# MCU.net
KiCad netlist of a schematic drawn in Altium Designer
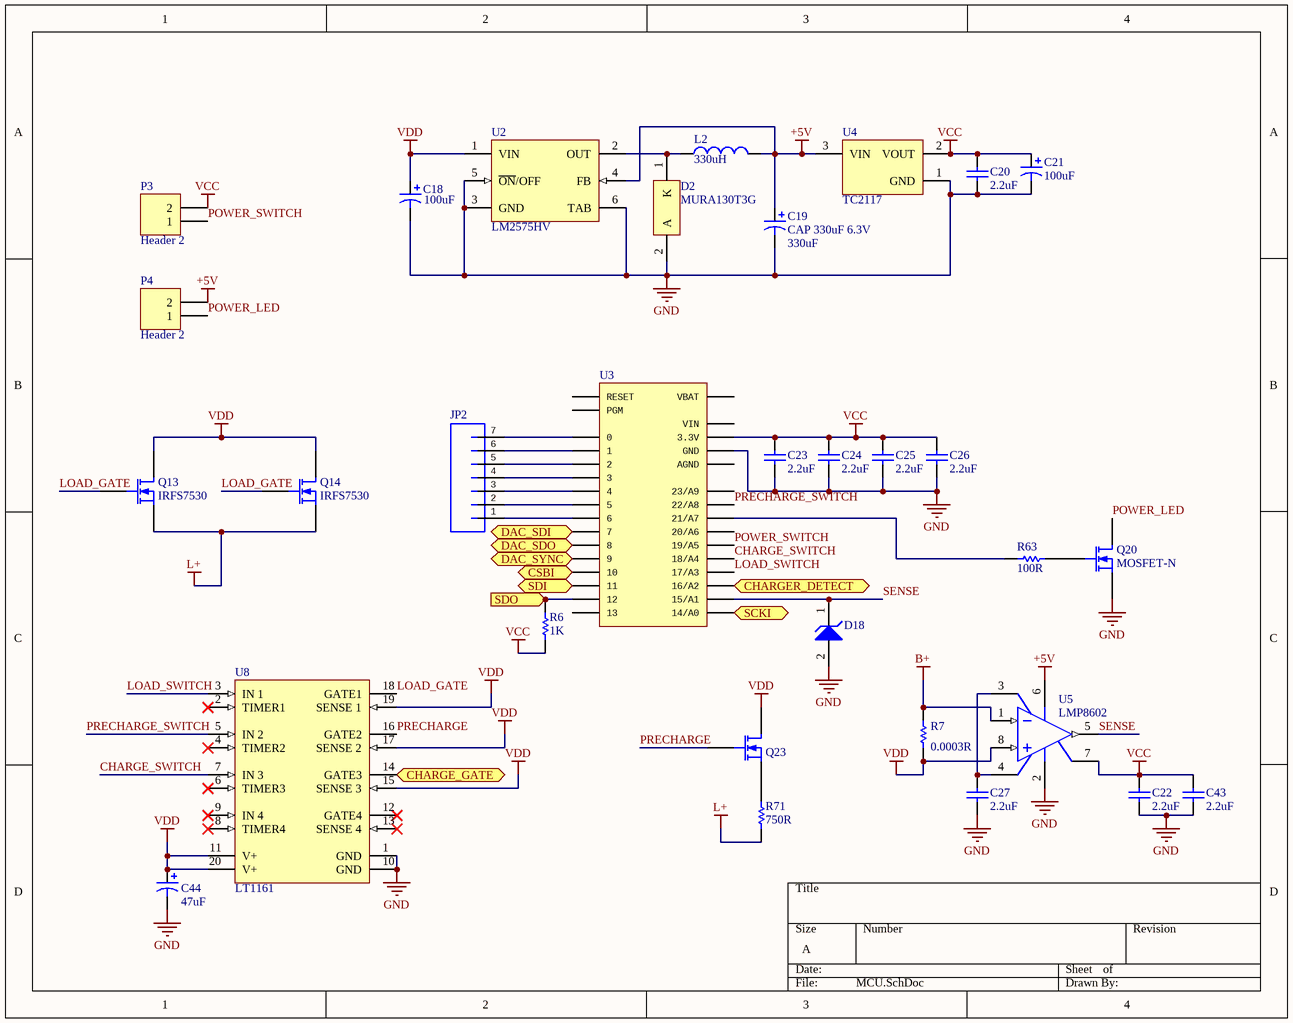
[diagram p0: MCU.SchDoc]

(export (version "E")
  (design (tool "Eeschema 10.0.6"))
  (components
    (comp (ref "C18")
      (value "100uF")
      (footprint "CAP 180uF 50V")
      (description "Polarized Capacitor (Axial)")
      (fields (field (name "PUBLISHER") "Altium Limited"))
      (libsource (lib "Components") (part "CAP 100uF 63V"))
    )
    (comp (ref "C19")
      (value "CAP 330uF 6.3V")
      (footprint "CAP 300uF 6.3V")
      (description "Polarized Capacitor (Axial)")
      (fields (field (name "ALTIUM_VALUE") "330uF") (field (name "PUBLISHER") "Altium Limited"))
      (libsource (lib "Components") (part "CAP 330uF 6.3V"))
    )
    (comp (ref "C20")
      (value "2.2uF")
      (footprint "CAPC0603(1608)55_N")
      (description "CAP 2.2uF 16V Â±10% 0603 (1608 Metric) Thickness 0.55mm SMD")
      (fields (field (name "TOLERANCE") "Â±10%"))
      (libsource (lib "Altium Content Vault") (part "CMP-1035-02762-1"))
    )
    (comp (ref "C21")
      (value "100uF")
      (footprint "AVX-CAPC7343_V")
      (description "Capacitor, Tantalum, 220uF 10% 10V MCCT-D (7343-31)")
      (fields (field (name "PARTNUMBER") "TAJD227K010R") (field (name "MANUFACTURER") "AVX"))
      (libsource (lib "Altium Content Vault") (part "CMP-0279-00002-1"))
    )
    (comp (ref "C22")
      (value "2.2uF")
      (footprint "CAPC0603(1608)55_M")
      (description "CAP 2.2uF 4V Â±10% 0603 (1608 Metric) Thickness 0.55mm SMD")
      (fields (field (name "TOLERANCE") "Â±10%"))
      (libsource (lib "Altium Content Vault") (part "CAP"))
    )
    (comp (ref "C23")
      (value "2.2uF")
      (footprint "CAPC0603(1608)55_N")
      (description "CAP 2.2uF 16V Â±10% 0603 (1608 Metric) Thickness 0.55mm SMD")
      (fields (field (name "TOLERANCE") "Â±10%"))
      (libsource (lib "Altium Content Vault") (part "CMP-1035-02762-1"))
    )
    (comp (ref "C24")
      (value "2.2uF")
      (footprint "CAPC0603(1608)55_N")
      (description "CAP 2.2uF 16V Â±10% 0603 (1608 Metric) Thickness 0.55mm SMD")
      (fields (field (name "TOLERANCE") "Â±10%"))
      (libsource (lib "Altium Content Vault") (part "CMP-1035-02762-1"))
    )
    (comp (ref "C25")
      (value "2.2uF")
      (footprint "CAPC0603(1608)55_N")
      (description "CAP 2.2uF 16V Â±10% 0603 (1608 Metric) Thickness 0.55mm SMD")
      (fields (field (name "TOLERANCE") "Â±10%"))
      (libsource (lib "Altium Content Vault") (part "CMP-1035-02762-1"))
    )
    (comp (ref "C26")
      (value "2.2uF")
      (footprint "CAPC0603(1608)55_N")
      (description "CAP 2.2uF 16V Â±10% 0603 (1608 Metric) Thickness 0.55mm SMD")
      (fields (field (name "TOLERANCE") "Â±10%"))
      (libsource (lib "Altium Content Vault") (part "CMP-1035-02762-1"))
    )
    (comp (ref "C27")
      (value "2.2uF")
      (footprint "CAPC0603(1608)55_N")
      (description "CAP 2.2uF 16V Â±10% 0603 (1608 Metric) Thickness 0.55mm SMD")
      (fields (field (name "TOLERANCE") "Â±10%"))
      (libsource (lib "Altium Content Vault") (part "CMP-1035-02762-1"))
    )
    (comp (ref "C43")
      (value "2.2uF")
      (footprint "CAPC0603(1608)55_M")
      (description "CAP 2.2uF 4V Â±10% 0603 (1608 Metric) Thickness 0.55mm SMD")
      (fields (field (name "TOLERANCE") "Â±10%"))
      (libsource (lib "Altium Content Vault") (part "CAP"))
    )
    (comp (ref "C44")
      (value "47uF")
      (footprint "CAP 300uF 6.3V")
      (description "Polarized Capacitor (Axial)")
      (fields (field (name "PUBLISHER") "Altium Limited"))
      (libsource (lib "Components") (part "CAP 47uF 50V"))
    )
    (comp (ref "D2")
      (value "MURA130T3G")
      (footprint "ONSC-SMA-2-403D-02_V")
      (description "Surface Mount Ultrafast Power Rectifier, 2-Pin SMA, Pb-Free, Tape and Reel")
      (fields (field (name "MANUFACTURER") "On Semiconductor"))
      (libsource (lib "Altium Content Vault") (part "ONSC-D-K1A2-2_A"))
    )
    (comp (ref "D18")
      (value "~")
      (footprint "ONSC-SOD-323-2-477-02_V")
      (description "Zener Voltage Regulator, 300 mW, Tight Tolerance Portfolio, 2-Pin SOD-323, Pb-Free, Tape and Reel")
      (fields (field (name "PARTNUMBER") "MM3Z3V3ST1G") (field (name "MANUFACTURER") "On Semiconductor"))
      (libsource (lib "Altium Inc") (part "ONSC-K1A2-2"))
    )
    (comp (ref "JP2") (value "~") (footprint "JST-7-PTH") (libsource (lib "Components") (part "JST_7_RIGHT")))
    (comp (ref "L2")
      (value "330uH")
      (footprint "SDR1307")
      (description "Inductor")
      (fields (field (name "PUBLISHER") "Altium Limited"))
      (libsource (lib "Components") (part "SDR1307-331KL"))
    )
    (comp (ref "P3")
      (value "Header 2")
      (footprint "HDR1X2")
      (description "Header, 2-Pin")
      (fields (field (name "PUBLISHER") "Altium Limited"))
      (libsource (lib "Miscellaneous Connectors") (part "Header 2"))
    )
    (comp (ref "P4")
      (value "Header 2")
      (footprint "HDR1X2")
      (description "Header, 2-Pin")
      (fields (field (name "PUBLISHER") "Altium Limited"))
      (libsource (lib "Miscellaneous Connectors") (part "Header 2"))
    )
    (comp (ref "Q13")
      (value "IRFS7530")
      (footprint "DPAK127P1525X483-7N")
      (description "N-Channel MOSFET")
      (fields (field (name "PUBLISHER") "Altium Limited"))
      (libsource (lib "Components") (part "IRFS7530"))
    )
    (comp (ref "Q14")
      (value "IRFS7530")
      (footprint "DPAK127P1525X483-7N")
      (description "N-Channel MOSFET")
      (fields (field (name "PUBLISHER") "Altium Limited"))
      (libsource (lib "Components") (part "IRFS7530"))
    )
    (comp (ref "Q20")
      (value "MOSFET-N")
      (footprint "SOT23-3")
      (description "N-Channel MOSFET")
      (fields (field (name "PUBLISHER") "Altium Limited"))
      (libsource (lib "Components") (part "MOSFET-N"))
    )
    (comp (ref "Q23")
      (value "MOSFET-N")
      (footprint "SOT23-3")
      (description "N-Channel MOSFET")
      (fields (field (name "PUBLISHER") "Altium Limited"))
      (libsource (lib "Components") (part "MOSFET-N"))
    )
    (comp (ref "R6")
      (value "1K")
      (footprint "RESC0603(1608)_L")
      (description "1K 0.1W 5% 0603 (1608 Metric)  SMD")
      (fields (field (name "TOLERANCE") "5 %") (field (name "POWER") "0.1 W"))
      (libsource (lib "Altium Content Vault") (part "RES"))
    )
    (comp (ref "R7")
      (value "0.0003R")
      (footprint "WSLP5931")
      (description "Resistor")
      (fields (field (name "PUBLISHER") "Altium Limited"))
      (libsource (lib "Components") (part "SHUNT"))
    )
    (comp (ref "R63")
      (value "100R")
      (footprint "RESC0603(1608)_L")
      (description "100R 0.1W 5% 0603 (1608 Metric)  SMD")
      (fields (field (name "TOLERANCE") "5 %") (field (name "POWER") "0.1 W"))
      (libsource (lib "Altium Content Vault") (part "RES"))
    )
    (comp (ref "R71")
      (value "750R")
      (footprint "RESC2512(6432)_N")
      (description "750R 1W 1% 2512 (6432 Metric)  SMD")
      (fields (field (name "TOLERANCE") "1 %") (field (name "POWER") "1 W"))
      (libsource (lib "Altium Content Vault") (part "RES"))
    )
    (comp (ref "U2")
      (value "LM2575HV")
      (footprint "TS5B_L")
      (description "SIMPLE SWITCHERÂ® 1A Step-Down Voltage Regulator, 5-pin TO-263, Pb-Free")
      (fields (field (name "MANUFACTURER") "National Semiconductor"))
      (libsource (lib "Altium Content Vault") (part "PM-REG-LM2575HVS-12"))
    )
    (comp (ref "U3")
      (value "~")
      (footprint "TEENSY_3.0_BASIC")
      (libsource (lib "Components") (part "TEENSY_3.0_BASIC"))
    )
    (comp (ref "U4")
      (value "TC2117")
      (footprint "SOT-223-DB3_M")
      (libsource (lib "Components") (part "PM-LINEREG-TC2117-IL4"))
    )
    (comp (ref "U5")
      (value "LMP8602")
      (footprint "M08A_M")
      (description "60V Common Mode, 50 x Gain, Bidirectional Precision Current Sensing Amplifier, 8 pin SOIC NARROW")
      (fields (field (name "MANUFACTURER") "National Semiconductor"))
      (libsource (lib "Altium Content Vault") (part "AMP-SEN-LMP8601-8"))
    )
    (comp (ref "U8")
      (value "LT1161")
      (footprint "LT-SW-20_N")
      (fields (field (name "MANUFACTURER") "Linear Technology") (field (name "PARTNUMBER") "LT1161ISW#PBF"))
      (libsource (lib "Altium Inc") (part "LT-LT1161-20"))
    )
  )
  (nets
    (net (code "1") (name "+5V") (class "Default")
      (node (ref "C19") (pin "1") (pinfunction "1_1") (pintype "passive"))
      (node (ref "L2") (pin "2") (pinfunction "2_2") (pintype "passive"))
      (node (ref "P4") (pin "2") (pinfunction "2_2") (pintype "passive"))
      (node (ref "U2") (pin "4") (pinfunction "FB_4") (pintype "input"))
      (node (ref "U4") (pin "3") (pinfunction "VIN_3") (pintype "power_in"))
      (node (ref "U5") (pin "6") (pinfunction "VS_6") (pintype "power_in"))
    )
    (net (code "2") (name "/CHARGER_DETECT") (class "Default")
      (node (ref "U3") (pin "16/A2") (pinfunction "16/A2_16/A2") (pintype "passive"))
    )
    (net (code "3") (name "/CHARGE_GATE") (class "Default")
      (node (ref "U8") (pin "14") (pinfunction "GATE3_14") (pintype "tri_state"))
    )
    (net (code "4") (name "/CHARGE_SWITCH") (class "Default")
      (node (ref "U3") (pin "18/A4") (pinfunction "18/A4_18/A4") (pintype "passive"))
      (node (ref "U8") (pin "7") (pinfunction "IN_3_7") (pintype "input"))
    )
    (net (code "5") (name "/CSBI") (class "Default")
      (node (ref "U3") (pin "10") (pinfunction "10_10") (pintype "passive"))
    )
    (net (code "6") (name "/DAC_SDI") (class "Default")
      (node (ref "U3") (pin "7") (pinfunction "7_7") (pintype "passive"))
    )
    (net (code "7") (name "/DAC_SDO") (class "Default")
      (node (ref "U3") (pin "8") (pinfunction "8_8") (pintype "passive"))
    )
    (net (code "8") (name "/DAC_SYNC") (class "Default")
      (node (ref "U3") (pin "9") (pinfunction "9_9") (pintype "passive"))
    )
    (net (code "9") (name "/LOAD_GATE") (class "Default")
      (node (ref "Q13") (pin "2") (pinfunction "G_2") (pintype "passive"))
      (node (ref "Q14") (pin "2") (pinfunction "G_2") (pintype "passive"))
      (node (ref "U8") (pin "18") (pinfunction "GATE1_18") (pintype "tri_state"))
    )
    (net (code "10") (name "/LOAD_SWITCH") (class "Default")
      (node (ref "U3") (pin "17/A3") (pinfunction "17/A3_17/A3") (pintype "passive"))
      (node (ref "U8") (pin "3") (pinfunction "IN_1_3") (pintype "input"))
    )
    (net (code "11") (name "/POWER_LED") (class "Default")
      (node (ref "P4") (pin "1") (pinfunction "1_1") (pintype "passive"))
      (node (ref "Q20") (pin "2") (pinfunction "D_2") (pintype "passive"))
    )
    (net (code "12") (name "/POWER_SWITCH") (class "Default")
      (node (ref "P3") (pin "1") (pinfunction "1_1") (pintype "passive"))
      (node (ref "U3") (pin "19/A5") (pinfunction "19/A5_19/A5") (pintype "passive"))
    )
    (net (code "13") (name "/PRECHARGE") (class "Default")
      (node (ref "Q23") (pin "1") (pinfunction "G_1") (pintype "passive"))
      (node (ref "U8") (pin "16") (pinfunction "GATE2_16") (pintype "tri_state"))
    )
    (net (code "14") (name "/PRECHARGE_SWITCH") (class "Default")
      (node (ref "U3") (pin "22/A8") (pinfunction "22/A8_22/A8") (pintype "passive"))
      (node (ref "U8") (pin "5") (pinfunction "IN_2_5") (pintype "input"))
    )
    (net (code "15") (name "/SCKI") (class "Default")
      (node (ref "U3") (pin "14/A0") (pinfunction "14/A0_14/A0") (pintype "passive"))
    )
    (net (code "16") (name "/SDI") (class "Default")
      (node (ref "U3") (pin "11") (pinfunction "11_11") (pintype "passive"))
    )
    (net (code "17") (name "/SDO") (class "Default")
      (node (ref "R6") (pin "2") (pinfunction "2_2") (pintype "passive"))
      (node (ref "U3") (pin "12") (pinfunction "12_12") (pintype "passive"))
    )
    (net (code "18") (name "/SENSE") (class "Default")
      (node (ref "D18") (pin "1") (pinfunction "K_1") (pintype "passive"))
      (node (ref "U3") (pin "15/A1") (pinfunction "15/A1_15/A1") (pintype "passive"))
      (node (ref "U5") (pin "5") (pinfunction "OUT_5") (pintype "output"))
    )
    (net (code "19") (name "B+") (class "Default")
      (node (ref "R7") (pin "2") (pinfunction "2_2") (pintype "passive"))
      (node (ref "U5") (pin "1") (pinfunction "IN-_1") (pintype "input"))
    )
    (net (code "20") (name "GND") (class "Default")
      (node (ref "C18") (pin "2") (pinfunction "2_2") (pintype "passive"))
      (node (ref "C19") (pin "2") (pinfunction "2_2") (pintype "passive"))
      (node (ref "C20") (pin "2") (pinfunction "2_2") (pintype "passive"))
      (node (ref "C21") (pin "2") (pinfunction "2_2") (pintype "passive"))
      (node (ref "C22") (pin "1") (pinfunction "1_1") (pintype "passive"))
      (node (ref "C23") (pin "1") (pinfunction "1_1") (pintype "passive"))
      (node (ref "C24") (pin "1") (pinfunction "1_1") (pintype "passive"))
      (node (ref "C25") (pin "1") (pinfunction "1_1") (pintype "passive"))
      (node (ref "C26") (pin "1") (pinfunction "1_1") (pintype "passive"))
      (node (ref "C27") (pin "1") (pinfunction "1_1") (pintype "passive"))
      (node (ref "C43") (pin "1") (pinfunction "1_1") (pintype "passive"))
      (node (ref "C44") (pin "2") (pinfunction "2_2") (pintype "passive"))
      (node (ref "D18") (pin "2") (pinfunction "A_2") (pintype "passive"))
      (node (ref "D2") (pin "2") (pinfunction "A_2") (pintype "passive"))
      (node (ref "Q20") (pin "3") (pinfunction "S_3") (pintype "passive"))
      (node (ref "U2") (pin "3") (pinfunction "GND_3") (pintype "power_in"))
      (node (ref "U2") (pin "5") (pinfunction "~{ON}/OFF_5") (pintype "input"))
      (node (ref "U2") (pin "6") (pinfunction "TAB_6") (pintype "power_in"))
      (node (ref "U3") (pin "GND_GND1") (pinfunction "GND_GND_GND1") (pintype "power_in"))
      (node (ref "U4") (pin "1") (pinfunction "GND_1") (pintype "power_in"))
      (node (ref "U5") (pin "2") (pinfunction "GND_2") (pintype "power_in"))
      (node (ref "U8") (pin "1") (pinfunction "GND_1") (pintype "power_in"))
      (node (ref "U8") (pin "10") (pinfunction "GND_10") (pintype "power_in"))
    )
    (net (code "21") (name "L+") (class "Default")
      (node (ref "Q13") (pin "3") (pinfunction "S_3") (pintype "passive"))
      (node (ref "Q14") (pin "3") (pinfunction "S_3") (pintype "passive"))
      (node (ref "R71") (pin "1") (pinfunction "1_1") (pintype "passive"))
    )
    (net (code "22") (name "Net-(D2-K)") (class "Default")
      (node (ref "D2") (pin "1") (pinfunction "K_1") (pintype "passive"))
      (node (ref "L2") (pin "1") (pinfunction "1_1") (pintype "passive"))
      (node (ref "U2") (pin "2") (pinfunction "OUT_2") (pintype "power_in"))
    )
    (net (code "23") (name "Net-(JP2-Pad1)") (class "Default")
      (node (ref "JP2") (pin "1") (pinfunction "1_1") (pintype "passive"))
      (node (ref "U3") (pin "6") (pinfunction "6_6") (pintype "passive"))
    )
    (net (code "24") (name "Net-(JP2-Pad2)") (class "Default")
      (node (ref "JP2") (pin "2") (pinfunction "2_2") (pintype "passive"))
      (node (ref "U3") (pin "5") (pinfunction "5_5") (pintype "passive"))
    )
    (net (code "25") (name "Net-(JP2-Pad3)") (class "Default")
      (node (ref "JP2") (pin "3") (pinfunction "3_3") (pintype "passive"))
      (node (ref "U3") (pin "4") (pinfunction "4_4") (pintype "passive"))
    )
    (net (code "26") (name "Net-(JP2-Pad4)") (class "Default")
      (node (ref "JP2") (pin "4") (pinfunction "4_4") (pintype "passive"))
      (node (ref "U3") (pin "3") (pinfunction "3_3") (pintype "passive"))
    )
    (net (code "27") (name "Net-(JP2-Pad5)") (class "Default")
      (node (ref "JP2") (pin "5") (pinfunction "5_5") (pintype "passive"))
      (node (ref "U3") (pin "2") (pinfunction "2_2") (pintype "passive"))
    )
    (net (code "28") (name "Net-(JP2-Pad6)") (class "Default")
      (node (ref "JP2") (pin "6") (pinfunction "6_6") (pintype "passive"))
      (node (ref "U3") (pin "1") (pinfunction "1_1") (pintype "passive"))
    )
    (net (code "29") (name "Net-(JP2-Pad7)") (class "Default")
      (node (ref "JP2") (pin "7") (pinfunction "7_7") (pintype "passive"))
      (node (ref "U3") (pin "0") (pinfunction "0_0") (pintype "passive"))
    )
    (net (code "30") (name "Net-(Q20-G)") (class "Default")
      (node (ref "Q20") (pin "1") (pinfunction "G_1") (pintype "passive"))
      (node (ref "R63") (pin "2") (pinfunction "2_2") (pintype "passive"))
    )
    (net (code "31") (name "Net-(Q23-S)") (class "Default")
      (node (ref "Q23") (pin "3") (pinfunction "S_3") (pintype "passive"))
      (node (ref "R71") (pin "2") (pinfunction "2_2") (pintype "passive"))
    )
    (net (code "32") (name "Net-(R63-Pad1)") (class "Default")
      (node (ref "R63") (pin "1") (pinfunction "1_1") (pintype "passive"))
      (node (ref "U3") (pin "21/A7") (pinfunction "21/A7_21/A7") (pintype "passive"))
    )
    (net (code "33") (name "Net-(U5-A1)") (class "Default")
      (node (ref "C27") (pin "2") (pinfunction "2_2") (pintype "passive"))
      (node (ref "U5") (pin "3") (pinfunction "A1_3") (pintype "passive"))
      (node (ref "U5") (pin "4") (pinfunction "A2_4") (pintype "passive"))
    )
    (net (code "34") (name "VCC") (class "Default")
      (node (ref "C20") (pin "1") (pinfunction "1_1") (pintype "passive"))
      (node (ref "C21") (pin "1") (pinfunction "1_1") (pintype "passive"))
      (node (ref "C22") (pin "2") (pinfunction "2_2") (pintype "passive"))
      (node (ref "C23") (pin "2") (pinfunction "2_2") (pintype "passive"))
      (node (ref "C24") (pin "2") (pinfunction "2_2") (pintype "passive"))
      (node (ref "C25") (pin "2") (pinfunction "2_2") (pintype "passive"))
      (node (ref "C26") (pin "2") (pinfunction "2_2") (pintype "passive"))
      (node (ref "C43") (pin "2") (pinfunction "2_2") (pintype "passive"))
      (node (ref "P3") (pin "2") (pinfunction "2_2") (pintype "passive"))
      (node (ref "R6") (pin "1") (pinfunction "1_1") (pintype "passive"))
      (node (ref "U3") (pin "3.3V_3.3V1") (pinfunction "3.3V_3.3V_3.3V1") (pintype "power_in"))
      (node (ref "U4") (pin "2") (pinfunction "VOUT_2") (pintype "power_in"))
      (node (ref "U5") (pin "7") (pinfunction "OFS_7") (pintype "passive"))
    )
    (net (code "35") (name "VDD") (class "Default")
      (node (ref "C18") (pin "1") (pinfunction "1_1") (pintype "passive"))
      (node (ref "C44") (pin "1") (pinfunction "1_1") (pintype "passive"))
      (node (ref "Q13") (pin "1") (pinfunction "D_1") (pintype "passive"))
      (node (ref "Q14") (pin "1") (pinfunction "D_1") (pintype "passive"))
      (node (ref "Q23") (pin "2") (pinfunction "D_2") (pintype "passive"))
      (node (ref "R7") (pin "1") (pinfunction "1_1") (pintype "passive"))
      (node (ref "U2") (pin "1") (pinfunction "VIN_1") (pintype "power_in"))
      (node (ref "U5") (pin "8") (pinfunction "IN+_8") (pintype "input"))
      (node (ref "U8") (pin "11") (pinfunction "V+_11") (pintype "power_in"))
      (node (ref "U8") (pin "15") (pinfunction "SENSE_3_15") (pintype "input"))
      (node (ref "U8") (pin "17") (pinfunction "SENSE_2_17") (pintype "input"))
      (node (ref "U8") (pin "19") (pinfunction "SENSE_1_19") (pintype "input"))
      (node (ref "U8") (pin "20") (pinfunction "V+_20") (pintype "power_in"))
    )
    (net (code "36") (name "unconnected-(U3-Pad13)") (class "Default")
      (node (ref "U3") (pin "13") (pinfunction "13_13") (pintype "passive"))
    )
    (net (code "37") (name "unconnected-(U3-Pad20{slash}A6)") (class "Default")
      (node (ref "U3") (pin "20/A6") (pinfunction "20/A6_20/A6") (pintype "passive"))
    )
    (net (code "38") (name "unconnected-(U3-Pad23{slash}A9)") (class "Default")
      (node (ref "U3") (pin "23/A9") (pinfunction "23/A9_23/A9") (pintype "passive"))
    )
    (net (code "39") (name "unconnected-(U3-PadAGND)") (class "Default")
      (node (ref "U3") (pin "AGND") (pinfunction "AGND_AGND") (pintype "power_in"))
    )
    (net (code "40") (name "unconnected-(U3-PadPGM)") (class "Default")
      (node (ref "U3") (pin "PGM") (pinfunction "PGM_PGM") (pintype "passive"))
    )
    (net (code "41") (name "unconnected-(U3-PadRESET)") (class "Default")
      (node (ref "U3") (pin "RESET") (pinfunction "RESET_RESET") (pintype "passive"))
    )
    (net (code "42") (name "unconnected-(U3-PadVBAT)") (class "Default")
      (node (ref "U3") (pin "VBAT") (pinfunction "VBAT_VBAT") (pintype "power_in"))
    )
    (net (code "43") (name "unconnected-(U3-PadVIN)") (class "Default")
      (node (ref "U3") (pin "VIN") (pinfunction "VIN_VIN") (pintype "power_in"))
    )
    (net (code "44") (name "unconnected-(U8-GATE4-Pad12)") (class "Default")
      (node (ref "U8") (pin "12") (pinfunction "GATE4_12") (pintype "tri_state+no_connect"))
    )
    (net (code "45") (name "unconnected-(U8-IN_4-Pad9)") (class "Default")
      (node (ref "U8") (pin "9") (pinfunction "IN_4_9") (pintype "input+no_connect"))
    )
    (net (code "46") (name "unconnected-(U8-SENSE_4-Pad13)") (class "Default")
      (node (ref "U8") (pin "13") (pinfunction "SENSE_4_13") (pintype "input+no_connect"))
    )
    (net (code "47") (name "unconnected-(U8-TIMER1-Pad2)") (class "Default")
      (node (ref "U8") (pin "2") (pinfunction "TIMER1_2") (pintype "input+no_connect"))
    )
    (net (code "48") (name "unconnected-(U8-TIMER2-Pad4)") (class "Default")
      (node (ref "U8") (pin "4") (pinfunction "TIMER2_4") (pintype "input+no_connect"))
    )
    (net (code "49") (name "unconnected-(U8-TIMER3-Pad6)") (class "Default")
      (node (ref "U8") (pin "6") (pinfunction "TIMER3_6") (pintype "input+no_connect"))
    )
    (net (code "50") (name "unconnected-(U8-TIMER4-Pad8)") (class "Default")
      (node (ref "U8") (pin "8") (pinfunction "TIMER4_8") (pintype "input+no_connect"))
    )
  )
)
